# 08_Peripherals.net
KiCad netlist of a schematic drawn in Altium Designer
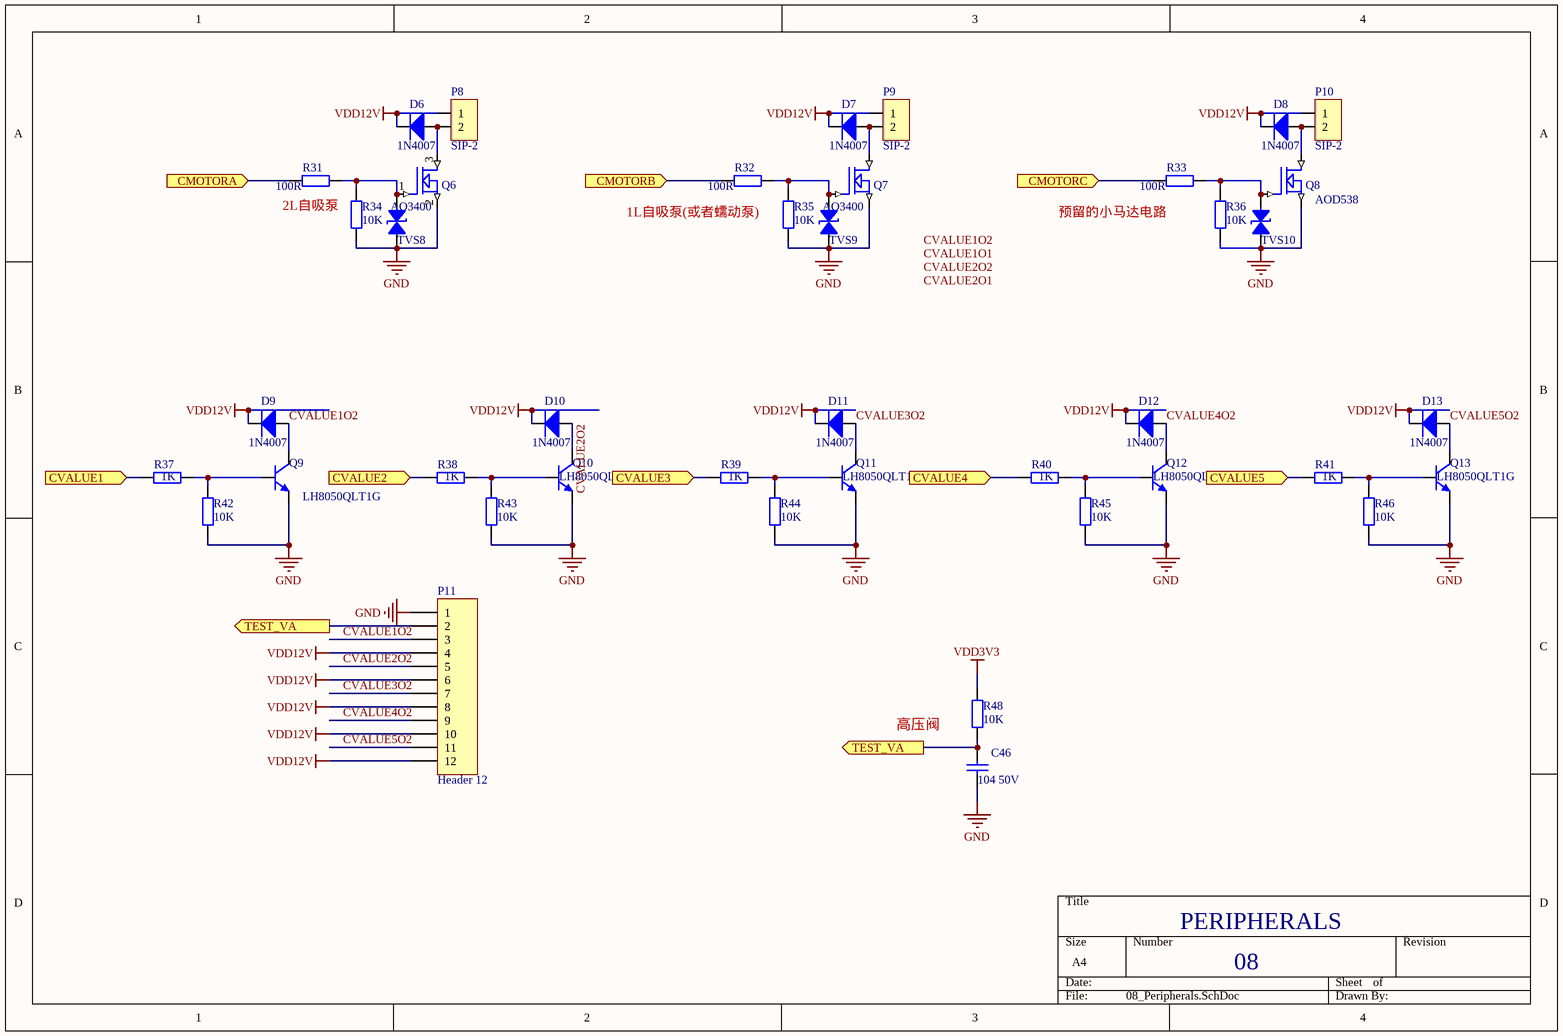
[diagram p0: 08_Peripherals.SchDoc]

(export (version "E")
  (design (tool "Eeschema 10.0.6"))
  (components
    (comp (ref "C46")
      (value "104 50V")
      (footprint "SMD-0603C")
      (description "贴片电容 10%")
      (libsource (lib "XiaoyI") (part "CAP4"))
    )
    (comp (ref "D6")
      (value "1N4007")
      (footprint "DO-214-AC")
      (description "贴片二极管")
      (libsource (lib "XiaoyI") (part "DIODE2"))
    )
    (comp (ref "D7")
      (value "1N4007")
      (footprint "DO-214-AC")
      (description "贴片二极管")
      (libsource (lib "XiaoyI") (part "DIODE2"))
    )
    (comp (ref "D8")
      (value "1N4007")
      (footprint "DO-214-AC")
      (description "贴片二极管")
      (libsource (lib "XiaoyI") (part "DIODE2"))
    )
    (comp (ref "D9")
      (value "1N4007")
      (footprint "DO-214-AC")
      (description "贴片二极管")
      (libsource (lib "XiaoyI") (part "DIODE2"))
    )
    (comp (ref "D10")
      (value "1N4007")
      (footprint "DO-214-AC")
      (description "贴片二极管")
      (libsource (lib "XiaoyI") (part "DIODE2"))
    )
    (comp (ref "D11")
      (value "1N4007")
      (footprint "DO-214-AC")
      (description "贴片二极管")
      (libsource (lib "XiaoyI") (part "DIODE2"))
    )
    (comp (ref "D12")
      (value "1N4007")
      (footprint "DO-214-AC")
      (description "贴片二极管")
      (libsource (lib "XiaoyI") (part "DIODE2"))
    )
    (comp (ref "D13")
      (value "1N4007")
      (footprint "DO-214-AC")
      (description "贴片二极管")
      (libsource (lib "XiaoyI") (part "DIODE2"))
    )
    (comp (ref "P8")
      (value "SIP-2")
      (footprint "SIP-2A")
      (description "XH2.54 2P 立贴")
      (libsource (lib "XiaoyI") (part "SIP-2"))
    )
    (comp (ref "P9")
      (value "SIP-2")
      (footprint "SIP-2A")
      (description "XH2.54 2P 立贴")
      (libsource (lib "XiaoyI") (part "SIP-2"))
    )
    (comp (ref "P10")
      (value "SIP-2")
      (footprint "VH-AW-3.96*2P")
      (description "XH2.54 2P 立贴")
      (libsource (lib "XiaoyI") (part "SIP-2"))
    )
    (comp (ref "P11")
      (value "Header 12")
      (footprint "12X2.54MMZ")
      (description "Header, 12-Pin")
      (fields (field (name "PUBLISHER") "Altium Limited"))
      (libsource (lib "Miscellaneous Connectors") (part "Header 12"))
    )
    (comp (ref "Q6")
      (value "AO3400")
      (footprint "SOT-23")
      (description "MOSFET N")
      (libsource (lib "") (part "MOSFET N_1"))
    )
    (comp (ref "Q7")
      (value "AO3400")
      (footprint "SOT-23")
      (description "MOSFET N")
      (libsource (lib "XiaoyI") (part "MOSFET N"))
    )
    (comp (ref "Q8")
      (value "AOD538")
      (footprint "TO252")
      (description "MOSFET N")
      (libsource (lib "XiaoyI") (part "MOSFET N"))
    )
    (comp (ref "Q9")
      (value "LH8050QLT1G")
      (footprint "SOT-23")
      (description "三极管")
      (libsource (lib "XiaoyI") (part "NPN-1"))
    )
    (comp (ref "Q10")
      (value "LH8050QLT1G")
      (footprint "SOT-23")
      (description "三极管")
      (libsource (lib "XiaoyI") (part "NPN-1"))
    )
    (comp (ref "Q11")
      (value "LH8050QLT1G")
      (footprint "SOT-23")
      (description "三极管")
      (libsource (lib "XiaoyI") (part "NPN-1"))
    )
    (comp (ref "Q12")
      (value "LH8050QLT1G")
      (footprint "SOT-23")
      (description "三极管")
      (libsource (lib "XiaoyI") (part "NPN-1"))
    )
    (comp (ref "Q13")
      (value "LH8050QLT1G")
      (footprint "SOT-23")
      (description "三极管")
      (libsource (lib "XiaoyI") (part "NPN-1"))
    )
    (comp (ref "R31")
      (value "100R")
      (footprint "SMD-0603")
      (description "贴片电阻 5%")
      (libsource (lib "XiaoyI") (part "RES-SOP"))
    )
    (comp (ref "R32")
      (value "100R")
      (footprint "SMD-0603")
      (description "贴片电阻 5%")
      (libsource (lib "XiaoyI") (part "RES-SOP"))
    )
    (comp (ref "R33")
      (value "100R")
      (footprint "SMD-0603")
      (description "贴片电阻 5%")
      (libsource (lib "XiaoyI") (part "RES-SOP"))
    )
    (comp (ref "R34")
      (value "10K")
      (footprint "SMD-0603")
      (description "贴片电阻 5%")
      (libsource (lib "") (part "RES-SOP_2"))
    )
    (comp (ref "R35")
      (value "10K")
      (footprint "SMD-0603")
      (description "贴片电阻 5%")
      (libsource (lib "") (part "RES-SOP_2"))
    )
    (comp (ref "R36")
      (value "10K")
      (footprint "SMD-0603")
      (description "贴片电阻 5%")
      (libsource (lib "") (part "RES-SOP_2"))
    )
    (comp (ref "R37")
      (value "1K")
      (footprint "SMD-0603")
      (description "贴片电阻 5%")
      (libsource (lib "XiaoyI") (part "RES-SOP"))
    )
    (comp (ref "R38")
      (value "1K")
      (footprint "SMD-0603")
      (description "贴片电阻 5%")
      (libsource (lib "XiaoyI") (part "RES-SOP"))
    )
    (comp (ref "R39")
      (value "1K")
      (footprint "SMD-0603")
      (description "贴片电阻 5%")
      (libsource (lib "XiaoyI") (part "RES-SOP"))
    )
    (comp (ref "R40")
      (value "1K")
      (footprint "SMD-0603")
      (description "贴片电阻 5%")
      (libsource (lib "XiaoyI") (part "RES-SOP"))
    )
    (comp (ref "R41")
      (value "1K")
      (footprint "SMD-0603")
      (description "贴片电阻 5%")
      (libsource (lib "XiaoyI") (part "RES-SOP"))
    )
    (comp (ref "R42")
      (value "10K")
      (footprint "SMD-0603")
      (description "贴片电阻 5%")
      (libsource (lib "") (part "RES-SOP_2"))
    )
    (comp (ref "R43")
      (value "10K")
      (footprint "SMD-0603")
      (description "贴片电阻 5%")
      (libsource (lib "") (part "RES-SOP_2"))
    )
    (comp (ref "R44")
      (value "10K")
      (footprint "SMD-0603")
      (description "贴片电阻 5%")
      (libsource (lib "") (part "RES-SOP_2"))
    )
    (comp (ref "R45")
      (value "10K")
      (footprint "SMD-0603")
      (description "贴片电阻 5%")
      (libsource (lib "") (part "RES-SOP_2"))
    )
    (comp (ref "R46")
      (value "10K")
      (footprint "SMD-0603")
      (description "贴片电阻 5%")
      (libsource (lib "") (part "RES-SOP_2"))
    )
    (comp (ref "R48")
      (value "10K")
      (footprint "SMD-0603")
      (description "贴片电阻 5%")
      (libsource (lib "") (part "RES-SOP_1"))
    )
    (comp (ref "TVS8")
      (value "ESD5Z5.0CT1G")
      (footprint "SOD-523")
      (description "TVS")
      (libsource (lib "XiaoyI") (part "TVS-1"))
    )
    (comp (ref "TVS9")
      (value "ESD5Z5.0CT1G")
      (footprint "SOD-523")
      (description "TVS")
      (libsource (lib "XiaoyI") (part "TVS-1"))
    )
    (comp (ref "TVS10")
      (value "ESD5Z5.0CT1G")
      (footprint "SOD-523")
      (description "TVS")
      (libsource (lib "XiaoyI") (part "TVS-1"))
    )
  )
  (nets
    (net (code "1") (name "/CMOTORA") (class "Default")
      (node (ref "R31") (pin "2") (pinfunction "2_2") (pintype "passive"))
    )
    (net (code "2") (name "/CMOTORB") (class "Default")
      (node (ref "R32") (pin "2") (pinfunction "2_2") (pintype "passive"))
    )
    (net (code "3") (name "/CMOTORC") (class "Default")
      (node (ref "R33") (pin "2") (pinfunction "2_2") (pintype "passive"))
    )
    (net (code "4") (name "/CVALUE1") (class "Default")
      (node (ref "R37") (pin "2") (pinfunction "2_2") (pintype "passive"))
    )
    (net (code "6") (name "/CVALUE1O2") (class "Default")
      (node (ref "D9") (pin "1") (pinfunction "A_1") (pintype "passive"))
      (node (ref "P11") (pin "3") (pinfunction "3_3") (pintype "passive"))
      (node (ref "Q9") (pin "3") (pinfunction "C_3") (pintype "passive"))
    )
    (net (code "7") (name "/CVALUE2") (class "Default")
      (node (ref "R38") (pin "2") (pinfunction "2_2") (pintype "passive"))
    )
    (net (code "9") (name "/CVALUE2O2") (class "Default")
      (node (ref "D10") (pin "1") (pinfunction "A_1") (pintype "passive"))
      (node (ref "P11") (pin "5") (pinfunction "5_5") (pintype "passive"))
      (node (ref "Q10") (pin "3") (pinfunction "C_3") (pintype "passive"))
    )
    (net (code "10") (name "/CVALUE3") (class "Default")
      (node (ref "R39") (pin "2") (pinfunction "2_2") (pintype "passive"))
    )
    (net (code "11") (name "/CVALUE3O2") (class "Default")
      (node (ref "D11") (pin "1") (pinfunction "A_1") (pintype "passive"))
      (node (ref "P11") (pin "7") (pinfunction "7_7") (pintype "passive"))
      (node (ref "Q11") (pin "3") (pinfunction "C_3") (pintype "passive"))
    )
    (net (code "12") (name "/CVALUE4") (class "Default")
      (node (ref "R40") (pin "2") (pinfunction "2_2") (pintype "passive"))
    )
    (net (code "13") (name "/CVALUE4O2") (class "Default")
      (node (ref "D12") (pin "1") (pinfunction "A_1") (pintype "passive"))
      (node (ref "P11") (pin "9") (pinfunction "9_9") (pintype "passive"))
      (node (ref "Q12") (pin "3") (pinfunction "C_3") (pintype "passive"))
    )
    (net (code "14") (name "/CVALUE5") (class "Default")
      (node (ref "R41") (pin "2") (pinfunction "2_2") (pintype "passive"))
    )
    (net (code "15") (name "/CVALUE5O2") (class "Default")
      (node (ref "D13") (pin "1") (pinfunction "A_1") (pintype "passive"))
      (node (ref "P11") (pin "11") (pinfunction "11_11") (pintype "passive"))
      (node (ref "Q13") (pin "3") (pinfunction "C_3") (pintype "passive"))
    )
    (net (code "16") (name "/TEST_VA") (class "Default")
      (node (ref "C46") (pin "2") (pinfunction "2_2") (pintype "passive"))
      (node (ref "P11") (pin "2") (pinfunction "2_2") (pintype "passive"))
      (node (ref "R48") (pin "1") (pinfunction "1_1") (pintype "passive"))
    )
    (net (code "17") (name "GND") (class "Default")
      (node (ref "C46") (pin "1") (pinfunction "1_1") (pintype "passive"))
      (node (ref "P11") (pin "1") (pinfunction "1_1") (pintype "passive"))
      (node (ref "Q10") (pin "2") (pinfunction "E_2") (pintype "passive"))
      (node (ref "Q11") (pin "2") (pinfunction "E_2") (pintype "passive"))
      (node (ref "Q12") (pin "2") (pinfunction "E_2") (pintype "passive"))
      (node (ref "Q13") (pin "2") (pinfunction "E_2") (pintype "passive"))
      (node (ref "Q6") (pin "2") (pinfunction "S_2") (pintype "output"))
      (node (ref "Q7") (pin "2") (pinfunction "S_2") (pintype "output"))
      (node (ref "Q8") (pin "2") (pinfunction "S_2") (pintype "output"))
      (node (ref "Q9") (pin "2") (pinfunction "E_2") (pintype "passive"))
      (node (ref "R34") (pin "2") (pinfunction "2_2") (pintype "passive"))
      (node (ref "R35") (pin "2") (pinfunction "2_2") (pintype "passive"))
      (node (ref "R36") (pin "2") (pinfunction "2_2") (pintype "passive"))
      (node (ref "R42") (pin "2") (pinfunction "2_2") (pintype "passive"))
      (node (ref "R43") (pin "2") (pinfunction "2_2") (pintype "passive"))
      (node (ref "R44") (pin "2") (pinfunction "2_2") (pintype "passive"))
      (node (ref "R45") (pin "2") (pinfunction "2_2") (pintype "passive"))
      (node (ref "R46") (pin "2") (pinfunction "2_2") (pintype "passive"))
      (node (ref "TVS10") (pin "1") (pinfunction "A_1") (pintype "passive"))
      (node (ref "TVS8") (pin "1") (pinfunction "A_1") (pintype "passive"))
      (node (ref "TVS9") (pin "1") (pinfunction "A_1") (pintype "passive"))
    )
    (net (code "18") (name "Net-(D6-A)") (class "Default")
      (node (ref "D6") (pin "1") (pinfunction "A_1") (pintype "passive"))
      (node (ref "P8") (pin "2") (pinfunction "2_2") (pintype "passive"))
      (node (ref "Q6") (pin "3") (pinfunction "D_3") (pintype "input"))
    )
    (net (code "19") (name "Net-(D7-A)") (class "Default")
      (node (ref "D7") (pin "1") (pinfunction "A_1") (pintype "passive"))
      (node (ref "P9") (pin "2") (pinfunction "2_2") (pintype "passive"))
      (node (ref "Q7") (pin "3") (pinfunction "D_3") (pintype "input"))
    )
    (net (code "20") (name "Net-(D8-A)") (class "Default")
      (node (ref "D8") (pin "1") (pinfunction "A_1") (pintype "passive"))
      (node (ref "P10") (pin "2") (pinfunction "2_2") (pintype "passive"))
      (node (ref "Q8") (pin "3") (pinfunction "D_3") (pintype "input"))
    )
    (net (code "21") (name "Net-(Q6-G)") (class "Default")
      (node (ref "Q6") (pin "1") (pinfunction "G_1") (pintype "input"))
      (node (ref "R31") (pin "1") (pinfunction "1_1") (pintype "passive"))
      (node (ref "R34") (pin "1") (pinfunction "1_1") (pintype "passive"))
      (node (ref "TVS8") (pin "2") (pinfunction "B_2") (pintype "passive"))
    )
    (net (code "22") (name "Net-(Q7-G)") (class "Default")
      (node (ref "Q7") (pin "1") (pinfunction "G_1") (pintype "input"))
      (node (ref "R32") (pin "1") (pinfunction "1_1") (pintype "passive"))
      (node (ref "R35") (pin "1") (pinfunction "1_1") (pintype "passive"))
      (node (ref "TVS9") (pin "2") (pinfunction "B_2") (pintype "passive"))
    )
    (net (code "23") (name "Net-(Q8-G)") (class "Default")
      (node (ref "Q8") (pin "1") (pinfunction "G_1") (pintype "input"))
      (node (ref "R33") (pin "1") (pinfunction "1_1") (pintype "passive"))
      (node (ref "R36") (pin "1") (pinfunction "1_1") (pintype "passive"))
      (node (ref "TVS10") (pin "2") (pinfunction "B_2") (pintype "passive"))
    )
    (net (code "24") (name "Net-(Q9-B)") (class "Default")
      (node (ref "Q9") (pin "1") (pinfunction "B_1") (pintype "passive"))
      (node (ref "R37") (pin "1") (pinfunction "1_1") (pintype "passive"))
      (node (ref "R42") (pin "1") (pinfunction "1_1") (pintype "passive"))
    )
    (net (code "25") (name "Net-(Q10-B)") (class "Default")
      (node (ref "Q10") (pin "1") (pinfunction "B_1") (pintype "passive"))
      (node (ref "R38") (pin "1") (pinfunction "1_1") (pintype "passive"))
      (node (ref "R43") (pin "1") (pinfunction "1_1") (pintype "passive"))
    )
    (net (code "26") (name "Net-(Q11-B)") (class "Default")
      (node (ref "Q11") (pin "1") (pinfunction "B_1") (pintype "passive"))
      (node (ref "R39") (pin "1") (pinfunction "1_1") (pintype "passive"))
      (node (ref "R44") (pin "1") (pinfunction "1_1") (pintype "passive"))
    )
    (net (code "27") (name "Net-(Q12-B)") (class "Default")
      (node (ref "Q12") (pin "1") (pinfunction "B_1") (pintype "passive"))
      (node (ref "R40") (pin "1") (pinfunction "1_1") (pintype "passive"))
      (node (ref "R45") (pin "1") (pinfunction "1_1") (pintype "passive"))
    )
    (net (code "28") (name "Net-(Q13-B)") (class "Default")
      (node (ref "Q13") (pin "1") (pinfunction "B_1") (pintype "passive"))
      (node (ref "R41") (pin "1") (pinfunction "1_1") (pintype "passive"))
      (node (ref "R46") (pin "1") (pinfunction "1_1") (pintype "passive"))
    )
    (net (code "29") (name "VDD3V3") (class "Default")
      (node (ref "R48") (pin "2") (pinfunction "2_2") (pintype "passive"))
    )
    (net (code "30") (name "VDD12V") (class "Default")
      (node (ref "D10") (pin "2") (pinfunction "K_2") (pintype "passive"))
      (node (ref "D11") (pin "2") (pinfunction "K_2") (pintype "passive"))
      (node (ref "D12") (pin "2") (pinfunction "K_2") (pintype "passive"))
      (node (ref "D13") (pin "2") (pinfunction "K_2") (pintype "passive"))
      (node (ref "D6") (pin "2") (pinfunction "K_2") (pintype "passive"))
      (node (ref "D7") (pin "2") (pinfunction "K_2") (pintype "passive"))
      (node (ref "D8") (pin "2") (pinfunction "K_2") (pintype "passive"))
      (node (ref "D9") (pin "2") (pinfunction "K_2") (pintype "passive"))
      (node (ref "P10") (pin "1") (pinfunction "1_1") (pintype "passive"))
      (node (ref "P11") (pin "10") (pinfunction "10_10") (pintype "passive"))
      (node (ref "P11") (pin "12") (pinfunction "12_12") (pintype "passive"))
      (node (ref "P11") (pin "4") (pinfunction "4_4") (pintype "passive"))
      (node (ref "P11") (pin "6") (pinfunction "6_6") (pintype "passive"))
      (node (ref "P11") (pin "8") (pinfunction "8_8") (pintype "passive"))
      (node (ref "P8") (pin "1") (pinfunction "1_1") (pintype "passive"))
      (node (ref "P9") (pin "1") (pinfunction "1_1") (pintype "passive"))
    )
  )
)
